# M220at.net
KiCad netlist of a schematic drawn in EAGLE
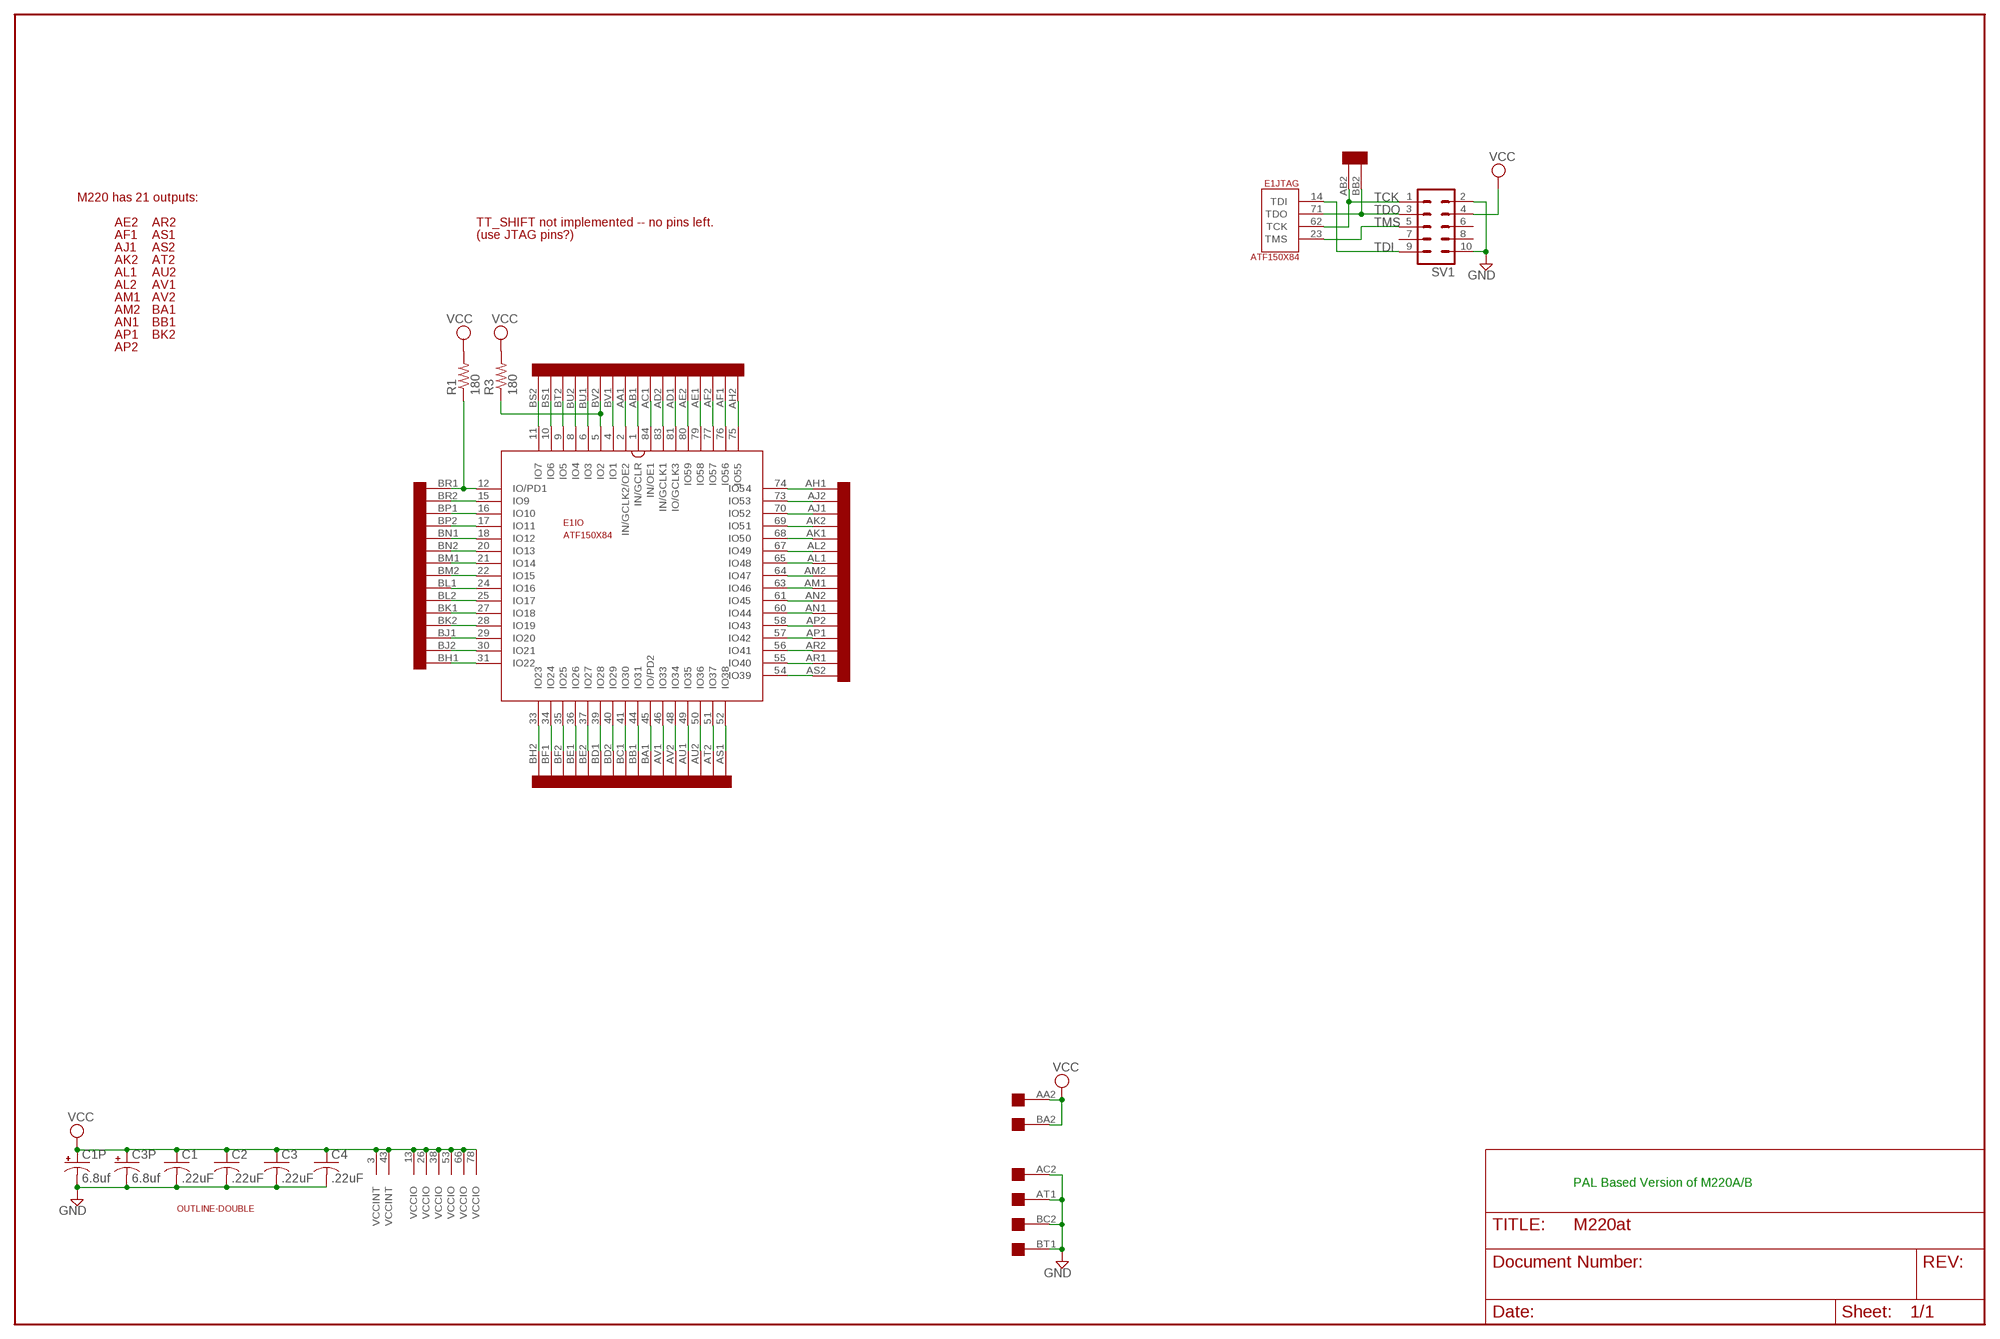
[diagram p0: schematic, sheet 1]

(export (version "E")
  (design (tool "Eeschema 10.0.6"))
  (components
    (comp (ref "C1")
      (value ".22uF")
      (footprint "eagle-import:C050-025X075")
      (libsource (lib "eagle-import") (part "C-US050-025X075"))
    )
    (comp (ref "C1P")
      (value "6.8uf")
      (footprint "eagle-import:E15-5")
      (libsource (lib "eagle-import") (part "CPOL-USE15-5AXIAL"))
    )
    (comp (ref "C2")
      (value ".22uF")
      (footprint "eagle-import:C050-025X075")
      (libsource (lib "eagle-import") (part "C-US050-025X075"))
    )
    (comp (ref "C3")
      (value ".22uF")
      (footprint "eagle-import:C050-025X075")
      (libsource (lib "eagle-import") (part "C-US050-025X075"))
    )
    (comp (ref "C3P")
      (value "6.8uf")
      (footprint "eagle-import:E15-5")
      (libsource (lib "eagle-import") (part "CPOL-USE15-5AXIAL"))
    )
    (comp (ref "C4")
      (value ".22uF")
      (footprint "eagle-import:C050-025X075")
      (libsource (lib "eagle-import") (part "C-US050-025X075"))
    )
    (comp (ref "E1")
      (value "ATF150X84")
      (footprint "eagle-import:S84")
      (libsource (lib "eagle-import") (part "ATF150X84"))
    )
    (comp (ref "R1")
      (value "180")
      (footprint "eagle-import:0207_10")
      (libsource (lib "eagle-import") (part "R-US_0207/10"))
    )
    (comp (ref "R3")
      (value "180")
      (footprint "eagle-import:0207_10")
      (libsource (lib "eagle-import") (part "R-US_0207/10"))
    )
    (comp (ref "SV1")
      (value "ML10")
      (footprint "eagle-import:ML10")
      (libsource (lib "eagle-import") (part "ML10"))
    )
    (comp (ref "U$1")
      (value "DOUBLE")
      (footprint "eagle-import:EDGE-CON4")
      (libsource (lib "eagle-import") (part "DOUBLE"))
    )
    (comp (ref "U$2")
      (value "OUTLINE-DOUBLE")
      (footprint "eagle-import:DOUBLE")
      (libsource (lib "eagle-import") (part "OUTLINE-DOUBLE"))
    )
  )
  (nets
    (net (code "1") (name "/TCK") (class "Default")
      (node (ref "E1") (pin "62") (pinfunction "TCK_62") (pintype "bidirectional"))
      (node (ref "SV1") (pin "1") (pinfunction "1_1") (pintype "passive"))
      (node (ref "U$1") (pin "AB2") (pinfunction "1_AB2") (pintype "bidirectional"))
    )
    (net (code "2") (name "/TDI") (class "Default")
      (node (ref "E1") (pin "14") (pinfunction "TDI_14") (pintype "bidirectional"))
      (node (ref "SV1") (pin "9") (pinfunction "9_9") (pintype "passive"))
    )
    (net (code "3") (name "/TDO") (class "Default")
      (node (ref "E1") (pin "71") (pinfunction "TDO_71") (pintype "bidirectional"))
      (node (ref "SV1") (pin "3") (pinfunction "3_3") (pintype "passive"))
      (node (ref "U$1") (pin "BB2") (pinfunction "1_BB2") (pintype "bidirectional"))
    )
    (net (code "4") (name "/TMS") (class "Default")
      (node (ref "E1") (pin "23") (pinfunction "TMS_23") (pintype "bidirectional"))
      (node (ref "SV1") (pin "5") (pinfunction "5_5") (pintype "passive"))
    )
    (net (code "5") (name "GND") (class "Default")
      (node (ref "C1") (pin "2") (pinfunction "2_2") (pintype "passive"))
      (node (ref "C1P") (pin "-") (pinfunction "-_-") (pintype "passive"))
      (node (ref "C2") (pin "2") (pinfunction "2_2") (pintype "passive"))
      (node (ref "C3") (pin "2") (pinfunction "2_2") (pintype "passive"))
      (node (ref "C3P") (pin "-") (pinfunction "-_-") (pintype "passive"))
      (node (ref "C4") (pin "2") (pinfunction "2_2") (pintype "passive"))
      (node (ref "SV1") (pin "10") (pinfunction "10_10") (pintype "passive"))
      (node (ref "SV1") (pin "2") (pinfunction "2_2") (pintype "passive"))
      (node (ref "U$1") (pin "AC2") (pinfunction "1_AC2") (pintype "bidirectional"))
      (node (ref "U$1") (pin "AT1") (pinfunction "1_AT1") (pintype "bidirectional"))
      (node (ref "U$1") (pin "BC2") (pinfunction "1_BC2") (pintype "bidirectional"))
      (node (ref "U$1") (pin "BT1") (pinfunction "1_BT1") (pintype "bidirectional"))
    )
    (net (code "6") (name "Net-(E1Q-IN{slash}GCLK1)") (class "Default")
      (node (ref "E1") (pin "83") (pinfunction "IN/GCLK1_83") (pintype "input"))
      (node (ref "U$1") (pin "AD2") (pinfunction "1_AD2") (pintype "bidirectional"))
    )
    (net (code "7") (name "Net-(E1Q-IN{slash}GCLK2{slash}OE2)") (class "Default")
      (node (ref "E1") (pin "2") (pinfunction "IN/GCLK2/OE2_2") (pintype "input"))
      (node (ref "U$1") (pin "AA1") (pinfunction "1_AA1") (pintype "bidirectional"))
    )
    (net (code "8") (name "Net-(E1Q-IN{slash}GCLR)") (class "Default")
      (node (ref "E1") (pin "1") (pinfunction "IN/GCLR_1") (pintype "input"))
      (node (ref "U$1") (pin "AB1") (pinfunction "1_AB1") (pintype "bidirectional"))
    )
    (net (code "9") (name "Net-(E1Q-IN{slash}OE1)") (class "Default")
      (node (ref "E1") (pin "84") (pinfunction "IN/OE1_84") (pintype "input"))
      (node (ref "U$1") (pin "AC1") (pinfunction "1_AC1") (pintype "bidirectional"))
    )
    (net (code "10") (name "Net-(E1Q-IO1)") (class "Default")
      (node (ref "E1") (pin "4") (pinfunction "IO1_4") (pintype "bidirectional"))
      (node (ref "U$1") (pin "BV1") (pinfunction "1_BV1") (pintype "bidirectional"))
    )
    (net (code "11") (name "Net-(E1Q-IO2)") (class "Default")
      (node (ref "E1") (pin "5") (pinfunction "IO2_5") (pintype "bidirectional"))
      (node (ref "R3") (pin "1") (pinfunction "1_1") (pintype "passive"))
      (node (ref "U$1") (pin "BV2") (pinfunction "1_BV2") (pintype "bidirectional"))
    )
    (net (code "12") (name "Net-(E1Q-IO3)") (class "Default")
      (node (ref "E1") (pin "6") (pinfunction "IO3_6") (pintype "bidirectional"))
      (node (ref "U$1") (pin "BU1") (pinfunction "1_BU1") (pintype "bidirectional"))
    )
    (net (code "13") (name "Net-(E1Q-IO4)") (class "Default")
      (node (ref "E1") (pin "8") (pinfunction "IO4_8") (pintype "bidirectional"))
      (node (ref "U$1") (pin "BU2") (pinfunction "1_BU2") (pintype "bidirectional"))
    )
    (net (code "14") (name "Net-(E1Q-IO5)") (class "Default")
      (node (ref "E1") (pin "9") (pinfunction "IO5_9") (pintype "bidirectional"))
      (node (ref "U$1") (pin "BT2") (pinfunction "1_BT2") (pintype "bidirectional"))
    )
    (net (code "15") (name "Net-(E1Q-IO6)") (class "Default")
      (node (ref "E1") (pin "10") (pinfunction "IO6_10") (pintype "bidirectional"))
      (node (ref "U$1") (pin "BS1") (pinfunction "1_BS1") (pintype "bidirectional"))
    )
    (net (code "16") (name "Net-(E1Q-IO7)") (class "Default")
      (node (ref "E1") (pin "11") (pinfunction "IO7_11") (pintype "bidirectional"))
      (node (ref "U$1") (pin "BS2") (pinfunction "1_BS2") (pintype "bidirectional"))
    )
    (net (code "17") (name "Net-(E1Q-IO9)") (class "Default")
      (node (ref "E1") (pin "15") (pinfunction "IO9_15") (pintype "bidirectional"))
      (node (ref "U$1") (pin "BR2") (pinfunction "1_BR2") (pintype "bidirectional"))
    )
    (net (code "18") (name "Net-(E1Q-IO10)") (class "Default")
      (node (ref "E1") (pin "16") (pinfunction "IO10_16") (pintype "bidirectional"))
      (node (ref "U$1") (pin "BP1") (pinfunction "1_BP1") (pintype "bidirectional"))
    )
    (net (code "19") (name "Net-(E1Q-IO11)") (class "Default")
      (node (ref "E1") (pin "17") (pinfunction "IO11_17") (pintype "bidirectional"))
      (node (ref "U$1") (pin "BP2") (pinfunction "1_BP2") (pintype "bidirectional"))
    )
    (net (code "20") (name "Net-(E1Q-IO12)") (class "Default")
      (node (ref "E1") (pin "18") (pinfunction "IO12_18") (pintype "bidirectional"))
      (node (ref "U$1") (pin "BN1") (pinfunction "1_BN1") (pintype "bidirectional"))
    )
    (net (code "21") (name "Net-(E1Q-IO13)") (class "Default")
      (node (ref "E1") (pin "20") (pinfunction "IO13_20") (pintype "bidirectional"))
      (node (ref "U$1") (pin "BN2") (pinfunction "1_BN2") (pintype "bidirectional"))
    )
    (net (code "22") (name "Net-(E1Q-IO14)") (class "Default")
      (node (ref "E1") (pin "21") (pinfunction "IO14_21") (pintype "bidirectional"))
      (node (ref "U$1") (pin "BM1") (pinfunction "1_BM1") (pintype "bidirectional"))
    )
    (net (code "23") (name "Net-(E1Q-IO15)") (class "Default")
      (node (ref "E1") (pin "22") (pinfunction "IO15_22") (pintype "bidirectional"))
      (node (ref "U$1") (pin "BM2") (pinfunction "1_BM2") (pintype "bidirectional"))
    )
    (net (code "24") (name "Net-(E1Q-IO16)") (class "Default")
      (node (ref "E1") (pin "24") (pinfunction "IO16_24") (pintype "bidirectional"))
      (node (ref "U$1") (pin "BL1") (pinfunction "1_BL1") (pintype "bidirectional"))
    )
    (net (code "25") (name "Net-(E1Q-IO17)") (class "Default")
      (node (ref "E1") (pin "25") (pinfunction "IO17_25") (pintype "bidirectional"))
      (node (ref "U$1") (pin "BL2") (pinfunction "1_BL2") (pintype "bidirectional"))
    )
    (net (code "26") (name "Net-(E1Q-IO18)") (class "Default")
      (node (ref "E1") (pin "27") (pinfunction "IO18_27") (pintype "bidirectional"))
      (node (ref "U$1") (pin "BK1") (pinfunction "1_BK1") (pintype "bidirectional"))
    )
    (net (code "27") (name "Net-(E1Q-IO19)") (class "Default")
      (node (ref "E1") (pin "28") (pinfunction "IO19_28") (pintype "bidirectional"))
      (node (ref "U$1") (pin "BK2") (pinfunction "1_BK2") (pintype "bidirectional"))
    )
    (net (code "28") (name "Net-(E1Q-IO20)") (class "Default")
      (node (ref "E1") (pin "29") (pinfunction "IO20_29") (pintype "bidirectional"))
      (node (ref "U$1") (pin "BJ1") (pinfunction "1_BJ1") (pintype "bidirectional"))
    )
    (net (code "29") (name "Net-(E1Q-IO21)") (class "Default")
      (node (ref "E1") (pin "30") (pinfunction "IO21_30") (pintype "bidirectional"))
      (node (ref "U$1") (pin "BJ2") (pinfunction "1_BJ2") (pintype "bidirectional"))
    )
    (net (code "30") (name "Net-(E1Q-IO22)") (class "Default")
      (node (ref "E1") (pin "31") (pinfunction "IO22_31") (pintype "bidirectional"))
      (node (ref "U$1") (pin "BH1") (pinfunction "1_BH1") (pintype "bidirectional"))
    )
    (net (code "31") (name "Net-(E1Q-IO23)") (class "Default")
      (node (ref "E1") (pin "33") (pinfunction "IO23_33") (pintype "bidirectional"))
      (node (ref "U$1") (pin "BH2") (pinfunction "1_BH2") (pintype "bidirectional"))
    )
    (net (code "32") (name "Net-(E1Q-IO24)") (class "Default")
      (node (ref "E1") (pin "34") (pinfunction "IO24_34") (pintype "bidirectional"))
      (node (ref "U$1") (pin "BF1") (pinfunction "1_BF1") (pintype "bidirectional"))
    )
    (net (code "33") (name "Net-(E1Q-IO25)") (class "Default")
      (node (ref "E1") (pin "35") (pinfunction "IO25_35") (pintype "bidirectional"))
      (node (ref "U$1") (pin "BF2") (pinfunction "1_BF2") (pintype "bidirectional"))
    )
    (net (code "34") (name "Net-(E1Q-IO26)") (class "Default")
      (node (ref "E1") (pin "36") (pinfunction "IO26_36") (pintype "bidirectional"))
      (node (ref "U$1") (pin "BE1") (pinfunction "1_BE1") (pintype "bidirectional"))
    )
    (net (code "35") (name "Net-(E1Q-IO27)") (class "Default")
      (node (ref "E1") (pin "37") (pinfunction "IO27_37") (pintype "bidirectional"))
      (node (ref "U$1") (pin "BE2") (pinfunction "1_BE2") (pintype "bidirectional"))
    )
    (net (code "36") (name "Net-(E1Q-IO28)") (class "Default")
      (node (ref "E1") (pin "39") (pinfunction "IO28_39") (pintype "bidirectional"))
      (node (ref "U$1") (pin "BD1") (pinfunction "1_BD1") (pintype "bidirectional"))
    )
    (net (code "37") (name "Net-(E1Q-IO29)") (class "Default")
      (node (ref "E1") (pin "40") (pinfunction "IO29_40") (pintype "bidirectional"))
      (node (ref "U$1") (pin "BD2") (pinfunction "1_BD2") (pintype "bidirectional"))
    )
    (net (code "38") (name "Net-(E1Q-IO30)") (class "Default")
      (node (ref "E1") (pin "41") (pinfunction "IO30_41") (pintype "bidirectional"))
      (node (ref "U$1") (pin "BC1") (pinfunction "1_BC1") (pintype "bidirectional"))
    )
    (net (code "39") (name "Net-(E1Q-IO31)") (class "Default")
      (node (ref "E1") (pin "44") (pinfunction "IO31_44") (pintype "bidirectional"))
      (node (ref "U$1") (pin "BB1") (pinfunction "1_BB1") (pintype "bidirectional"))
    )
    (net (code "40") (name "Net-(E1Q-IO33)") (class "Default")
      (node (ref "E1") (pin "46") (pinfunction "IO33_46") (pintype "bidirectional"))
      (node (ref "U$1") (pin "AV1") (pinfunction "1_AV1") (pintype "bidirectional"))
    )
    (net (code "41") (name "Net-(E1Q-IO34)") (class "Default")
      (node (ref "E1") (pin "48") (pinfunction "IO34_48") (pintype "bidirectional"))
      (node (ref "U$1") (pin "AV2") (pinfunction "1_AV2") (pintype "bidirectional"))
    )
    (net (code "42") (name "Net-(E1Q-IO35)") (class "Default")
      (node (ref "E1") (pin "49") (pinfunction "IO35_49") (pintype "bidirectional"))
      (node (ref "U$1") (pin "AU1") (pinfunction "1_AU1") (pintype "bidirectional"))
    )
    (net (code "43") (name "Net-(E1Q-IO36)") (class "Default")
      (node (ref "E1") (pin "50") (pinfunction "IO36_50") (pintype "bidirectional"))
      (node (ref "U$1") (pin "AU2") (pinfunction "1_AU2") (pintype "bidirectional"))
    )
    (net (code "44") (name "Net-(E1Q-IO37)") (class "Default")
      (node (ref "E1") (pin "51") (pinfunction "IO37_51") (pintype "bidirectional"))
      (node (ref "U$1") (pin "AT2") (pinfunction "1_AT2") (pintype "bidirectional"))
    )
    (net (code "45") (name "Net-(E1Q-IO38)") (class "Default")
      (node (ref "E1") (pin "52") (pinfunction "IO38_52") (pintype "bidirectional"))
      (node (ref "U$1") (pin "AS1") (pinfunction "1_AS1") (pintype "bidirectional"))
    )
    (net (code "46") (name "Net-(E1Q-IO39)") (class "Default")
      (node (ref "E1") (pin "54") (pinfunction "IO39_54") (pintype "bidirectional"))
      (node (ref "U$1") (pin "AS2") (pinfunction "1_AS2") (pintype "bidirectional"))
    )
    (net (code "47") (name "Net-(E1Q-IO40)") (class "Default")
      (node (ref "E1") (pin "55") (pinfunction "IO40_55") (pintype "bidirectional"))
      (node (ref "U$1") (pin "AR1") (pinfunction "1_AR1") (pintype "bidirectional"))
    )
    (net (code "48") (name "Net-(E1Q-IO41)") (class "Default")
      (node (ref "E1") (pin "56") (pinfunction "IO41_56") (pintype "bidirectional"))
      (node (ref "U$1") (pin "AR2") (pinfunction "1_AR2") (pintype "bidirectional"))
    )
    (net (code "49") (name "Net-(E1Q-IO42)") (class "Default")
      (node (ref "E1") (pin "57") (pinfunction "IO42_57") (pintype "bidirectional"))
      (node (ref "U$1") (pin "AP1") (pinfunction "1_AP1") (pintype "bidirectional"))
    )
    (net (code "50") (name "Net-(E1Q-IO43)") (class "Default")
      (node (ref "E1") (pin "58") (pinfunction "IO43_58") (pintype "bidirectional"))
      (node (ref "U$1") (pin "AP2") (pinfunction "1_AP2") (pintype "bidirectional"))
    )
    (net (code "51") (name "Net-(E1Q-IO44)") (class "Default")
      (node (ref "E1") (pin "60") (pinfunction "IO44_60") (pintype "bidirectional"))
      (node (ref "U$1") (pin "AN1") (pinfunction "1_AN1") (pintype "bidirectional"))
    )
    (net (code "52") (name "Net-(E1Q-IO45)") (class "Default")
      (node (ref "E1") (pin "61") (pinfunction "IO45_61") (pintype "bidirectional"))
      (node (ref "U$1") (pin "AN2") (pinfunction "1_AN2") (pintype "bidirectional"))
    )
    (net (code "53") (name "Net-(E1Q-IO46)") (class "Default")
      (node (ref "E1") (pin "63") (pinfunction "IO46_63") (pintype "bidirectional"))
      (node (ref "U$1") (pin "AM1") (pinfunction "1_AM1") (pintype "bidirectional"))
    )
    (net (code "54") (name "Net-(E1Q-IO47)") (class "Default")
      (node (ref "E1") (pin "64") (pinfunction "IO47_64") (pintype "bidirectional"))
      (node (ref "U$1") (pin "AM2") (pinfunction "1_AM2") (pintype "bidirectional"))
    )
    (net (code "55") (name "Net-(E1Q-IO48)") (class "Default")
      (node (ref "E1") (pin "65") (pinfunction "IO48_65") (pintype "bidirectional"))
      (node (ref "U$1") (pin "AL1") (pinfunction "1_AL1") (pintype "bidirectional"))
    )
    (net (code "56") (name "Net-(E1Q-IO49)") (class "Default")
      (node (ref "E1") (pin "67") (pinfunction "IO49_67") (pintype "bidirectional"))
      (node (ref "U$1") (pin "AL2") (pinfunction "1_AL2") (pintype "bidirectional"))
    )
    (net (code "57") (name "Net-(E1Q-IO50)") (class "Default")
      (node (ref "E1") (pin "68") (pinfunction "IO50_68") (pintype "bidirectional"))
      (node (ref "U$1") (pin "AK1") (pinfunction "1_AK1") (pintype "bidirectional"))
    )
    (net (code "58") (name "Net-(E1Q-IO51)") (class "Default")
      (node (ref "E1") (pin "69") (pinfunction "IO51_69") (pintype "bidirectional"))
      (node (ref "U$1") (pin "AK2") (pinfunction "1_AK2") (pintype "bidirectional"))
    )
    (net (code "59") (name "Net-(E1Q-IO52)") (class "Default")
      (node (ref "E1") (pin "70") (pinfunction "IO52_70") (pintype "bidirectional"))
      (node (ref "U$1") (pin "AJ1") (pinfunction "1_AJ1") (pintype "bidirectional"))
    )
    (net (code "60") (name "Net-(E1Q-IO53)") (class "Default")
      (node (ref "E1") (pin "73") (pinfunction "IO53_73") (pintype "bidirectional"))
      (node (ref "U$1") (pin "AJ2") (pinfunction "1_AJ2") (pintype "bidirectional"))
    )
    (net (code "61") (name "Net-(E1Q-IO54)") (class "Default")
      (node (ref "E1") (pin "74") (pinfunction "IO54_74") (pintype "bidirectional"))
      (node (ref "U$1") (pin "AH1") (pinfunction "1_AH1") (pintype "bidirectional"))
    )
    (net (code "62") (name "Net-(E1Q-IO55)") (class "Default")
      (node (ref "E1") (pin "75") (pinfunction "IO55_75") (pintype "bidirectional"))
      (node (ref "U$1") (pin "AH2") (pinfunction "1_AH2") (pintype "bidirectional"))
    )
    (net (code "63") (name "Net-(E1Q-IO56)") (class "Default")
      (node (ref "E1") (pin "76") (pinfunction "IO56_76") (pintype "bidirectional"))
      (node (ref "U$1") (pin "AF1") (pinfunction "1_AF1") (pintype "bidirectional"))
    )
    (net (code "64") (name "Net-(E1Q-IO57)") (class "Default")
      (node (ref "E1") (pin "77") (pinfunction "IO57_77") (pintype "bidirectional"))
      (node (ref "U$1") (pin "AF2") (pinfunction "1_AF2") (pintype "bidirectional"))
    )
    (net (code "65") (name "Net-(E1Q-IO58)") (class "Default")
      (node (ref "E1") (pin "79") (pinfunction "IO58_79") (pintype "bidirectional"))
      (node (ref "U$1") (pin "AE1") (pinfunction "1_AE1") (pintype "bidirectional"))
    )
    (net (code "66") (name "Net-(E1Q-IO59)") (class "Default")
      (node (ref "E1") (pin "80") (pinfunction "IO59_80") (pintype "bidirectional"))
      (node (ref "U$1") (pin "AE2") (pinfunction "1_AE2") (pintype "bidirectional"))
    )
    (net (code "67") (name "Net-(E1Q-IO{slash}GCLK3)") (class "Default")
      (node (ref "E1") (pin "81") (pinfunction "IO/GCLK3_81") (pintype "bidirectional"))
      (node (ref "U$1") (pin "AD1") (pinfunction "1_AD1") (pintype "bidirectional"))
    )
    (net (code "68") (name "Net-(E1Q-IO{slash}PD1)") (class "Default")
      (node (ref "E1") (pin "12") (pinfunction "IO/PD1_12") (pintype "bidirectional"))
      (node (ref "R1") (pin "1") (pinfunction "1_1") (pintype "passive"))
      (node (ref "U$1") (pin "BR1") (pinfunction "1_BR1") (pintype "bidirectional"))
    )
    (net (code "69") (name "Net-(E1Q-IO{slash}PD2)") (class "Default")
      (node (ref "E1") (pin "45") (pinfunction "IO/PD2_45") (pintype "bidirectional"))
      (node (ref "U$1") (pin "BA1") (pinfunction "1_BA1") (pintype "bidirectional"))
    )
    (net (code "70") (name "VCC") (class "Default")
      (node (ref "C1") (pin "1") (pinfunction "1_1") (pintype "passive"))
      (node (ref "C1P") (pin "+") (pinfunction "+_+") (pintype "passive"))
      (node (ref "C2") (pin "1") (pinfunction "1_1") (pintype "passive"))
      (node (ref "C3") (pin "1") (pinfunction "1_1") (pintype "passive"))
      (node (ref "C3P") (pin "+") (pinfunction "+_+") (pintype "passive"))
      (node (ref "C4") (pin "1") (pinfunction "1_1") (pintype "passive"))
      (node (ref "E1") (pin "13") (pinfunction "VCCIO_13") (pintype "power_in"))
      (node (ref "E1") (pin "26") (pinfunction "VCCIO_26") (pintype "power_in"))
      (node (ref "E1") (pin "3") (pinfunction "VCCINT_3") (pintype "power_in"))
      (node (ref "E1") (pin "38") (pinfunction "VCCIO_38") (pintype "power_in"))
      (node (ref "E1") (pin "43") (pinfunction "VCCINT_43") (pintype "power_in"))
      (node (ref "E1") (pin "53") (pinfunction "VCCIO_53") (pintype "power_in"))
      (node (ref "E1") (pin "66") (pinfunction "VCCIO_66") (pintype "power_in"))
      (node (ref "E1") (pin "78") (pinfunction "VCCIO_78") (pintype "power_in"))
      (node (ref "R1") (pin "2") (pinfunction "2_2") (pintype "passive"))
      (node (ref "R3") (pin "2") (pinfunction "2_2") (pintype "passive"))
      (node (ref "SV1") (pin "4") (pinfunction "4_4") (pintype "passive"))
      (node (ref "U$1") (pin "AA2") (pinfunction "1_AA2") (pintype "bidirectional"))
      (node (ref "U$1") (pin "BA2") (pinfunction "1_BA2") (pintype "bidirectional"))
    )
    (net (code "71") (name "unconnected-(SV1-Pad6)") (class "Default")
      (node (ref "SV1") (pin "6") (pinfunction "6_6") (pintype "passive"))
    )
    (net (code "72") (name "unconnected-(SV1-Pad7)") (class "Default")
      (node (ref "SV1") (pin "7") (pinfunction "7_7") (pintype "passive"))
    )
    (net (code "73") (name "unconnected-(SV1-Pad8)") (class "Default")
      (node (ref "SV1") (pin "8") (pinfunction "8_8") (pintype "passive"))
    )
  )
)
